# vu_esquema.net
KiCad netlist of a schematic drawn in EAGLE
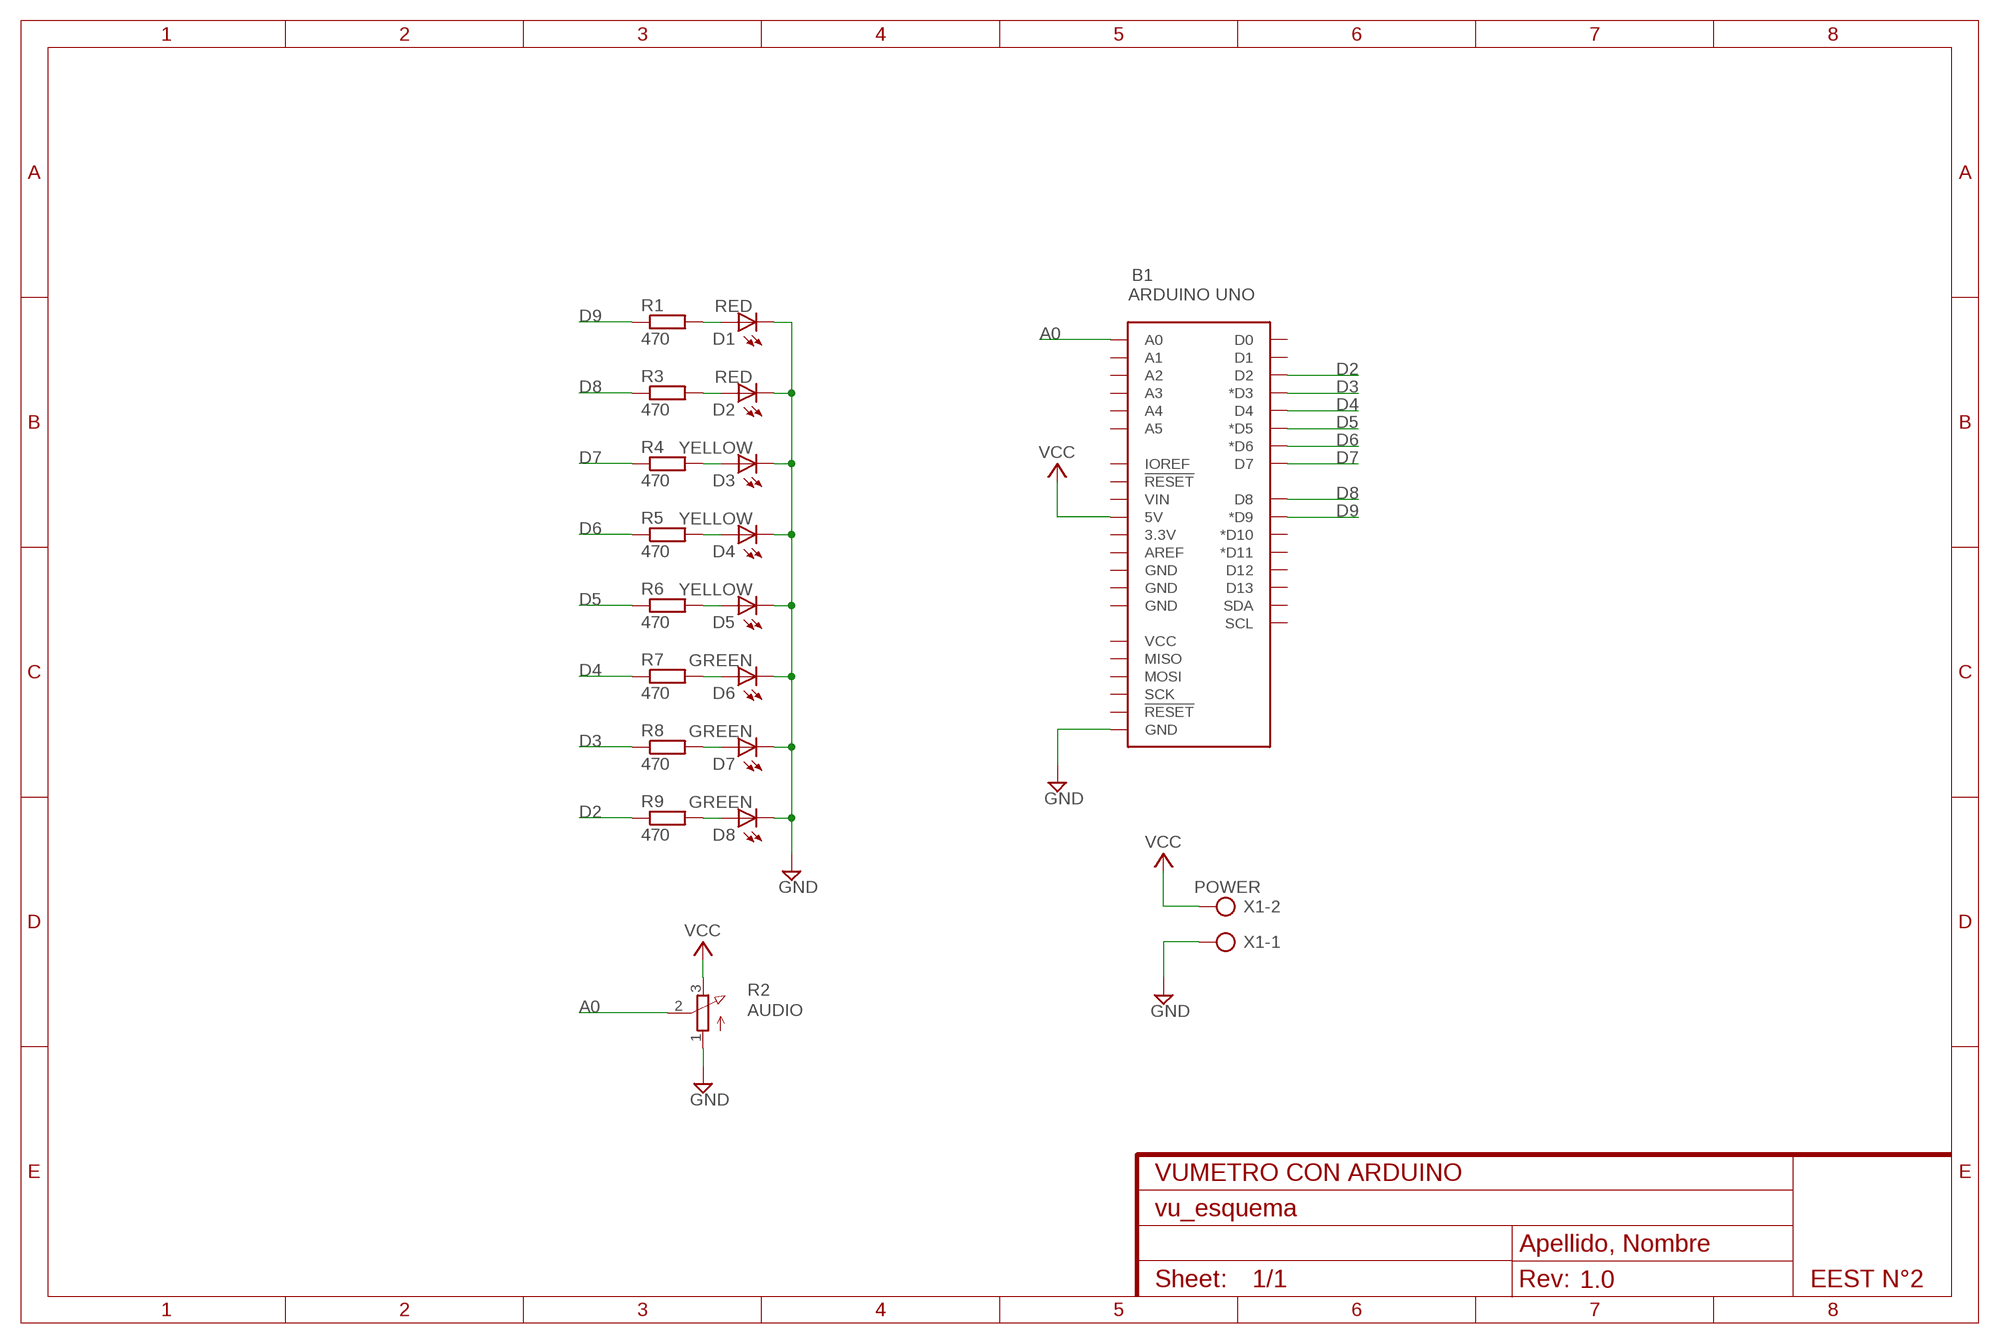
[diagram p0: schematic, sheet 1]

(export (version "E")
  (design (tool "Eeschema 10.0.6"))
  (components
    (comp (ref "B1")
      (value "ARDUINO UNO")
      (footprint "eagle-import:ARDUINO_R3")
      (libsource (lib "eagle-import") (part "ARDUINO_UNO_R3"))
    )
    (comp (ref "D1")
      (value "RED")
      (footprint "eagle-import:LED_5MM")
      (libsource (lib "eagle-import") (part "LED5MM"))
    )
    (comp (ref "D2")
      (value "RED")
      (footprint "eagle-import:LED_5MM")
      (libsource (lib "eagle-import") (part "LED5MM"))
    )
    (comp (ref "D3")
      (value "YELLOW")
      (footprint "eagle-import:LED_5MM")
      (libsource (lib "eagle-import") (part "LED5MM"))
    )
    (comp (ref "D4")
      (value "YELLOW")
      (footprint "eagle-import:LED_5MM")
      (libsource (lib "eagle-import") (part "LED5MM"))
    )
    (comp (ref "D5")
      (value "YELLOW")
      (footprint "eagle-import:LED_5MM")
      (libsource (lib "eagle-import") (part "LED5MM"))
    )
    (comp (ref "D6")
      (value "GREEN")
      (footprint "eagle-import:LED_5MM")
      (libsource (lib "eagle-import") (part "LED5MM"))
    )
    (comp (ref "D7")
      (value "GREEN")
      (footprint "eagle-import:LED_5MM")
      (libsource (lib "eagle-import") (part "LED5MM"))
    )
    (comp (ref "D8")
      (value "GREEN")
      (footprint "eagle-import:LED_5MM")
      (libsource (lib "eagle-import") (part "LED5MM"))
    )
    (comp (ref "R1")
      (value "470")
      (footprint "eagle-import:0204_7")
      (libsource (lib "eagle-import") (part "RESISTOR-EU0204/7"))
    )
    (comp (ref "R2")
      (value "AUDIO")
      (footprint "eagle-import:3RP_1610N")
      (libsource (lib "eagle-import") (part "3RP/1610N"))
    )
    (comp (ref "R3")
      (value "470")
      (footprint "eagle-import:0204_7")
      (libsource (lib "eagle-import") (part "RESISTOR-EU0204/7"))
    )
    (comp (ref "R4")
      (value "470")
      (footprint "eagle-import:0204_7")
      (libsource (lib "eagle-import") (part "RESISTOR-EU0204/7"))
    )
    (comp (ref "R5")
      (value "470")
      (footprint "eagle-import:0204_7")
      (libsource (lib "eagle-import") (part "RESISTOR-EU0204/7"))
    )
    (comp (ref "R6")
      (value "470")
      (footprint "eagle-import:0204_7")
      (libsource (lib "eagle-import") (part "RESISTOR-EU0204/7"))
    )
    (comp (ref "R7")
      (value "470")
      (footprint "eagle-import:0204_7")
      (libsource (lib "eagle-import") (part "RESISTOR-EU0204/7"))
    )
    (comp (ref "R8")
      (value "470")
      (footprint "eagle-import:0204_7")
      (libsource (lib "eagle-import") (part "RESISTOR-EU0204/7"))
    )
    (comp (ref "R9")
      (value "470")
      (footprint "eagle-import:0204_7")
      (libsource (lib "eagle-import") (part "RESISTOR-EU0204/7"))
    )
    (comp (ref "X1")
      (value "POWER")
      (footprint "eagle-import:AK500_2")
      (libsource (lib "eagle-import") (part "BORNERA_AK500/2"))
    )
  )
  (nets
    (net (code "1") (name "/A0") (class "Default")
      (node (ref "B1") (pin "A0") (pinfunction "A0_A0") (pintype "bidirectional"))
      (node (ref "R2") (pin "2") (pinfunction "S_2") (pintype "passive"))
    )
    (net (code "2") (name "/D2") (class "Default")
      (node (ref "B1") (pin "D2") (pinfunction "D2_D2") (pintype "bidirectional"))
      (node (ref "R9") (pin "1") (pinfunction "1_1") (pintype "passive"))
    )
    (net (code "3") (name "/D3") (class "Default")
      (node (ref "B1") (pin "D3") (pinfunction "*D3_D3") (pintype "bidirectional"))
      (node (ref "R8") (pin "1") (pinfunction "1_1") (pintype "passive"))
    )
    (net (code "4") (name "/D4") (class "Default")
      (node (ref "B1") (pin "D4") (pinfunction "D4_D4") (pintype "bidirectional"))
      (node (ref "R7") (pin "1") (pinfunction "1_1") (pintype "passive"))
    )
    (net (code "5") (name "/D5") (class "Default")
      (node (ref "B1") (pin "D5") (pinfunction "*D5_D5") (pintype "bidirectional"))
      (node (ref "R6") (pin "1") (pinfunction "1_1") (pintype "passive"))
    )
    (net (code "6") (name "/D6") (class "Default")
      (node (ref "B1") (pin "D6") (pinfunction "*D6_D6") (pintype "bidirectional"))
      (node (ref "R5") (pin "1") (pinfunction "1_1") (pintype "passive"))
    )
    (net (code "7") (name "/D7") (class "Default")
      (node (ref "B1") (pin "D7") (pinfunction "D7_D7") (pintype "bidirectional"))
      (node (ref "R4") (pin "1") (pinfunction "1_1") (pintype "passive"))
    )
    (net (code "8") (name "/D8") (class "Default")
      (node (ref "B1") (pin "D8") (pinfunction "D8_D8") (pintype "bidirectional"))
      (node (ref "R3") (pin "1") (pinfunction "1_1") (pintype "passive"))
    )
    (net (code "9") (name "/D9") (class "Default")
      (node (ref "B1") (pin "D9") (pinfunction "*D9_D9") (pintype "bidirectional"))
      (node (ref "R1") (pin "1") (pinfunction "1_1") (pintype "passive"))
    )
    (net (code "10") (name "GND") (class "Default")
      (node (ref "B1") (pin "GND@1") (pinfunction "GND_GND@1") (pintype "bidirectional"))
      (node (ref "D1") (pin "K") (pinfunction "C_K") (pintype "passive"))
      (node (ref "D2") (pin "K") (pinfunction "C_K") (pintype "passive"))
      (node (ref "D3") (pin "K") (pinfunction "C_K") (pintype "passive"))
      (node (ref "D4") (pin "K") (pinfunction "C_K") (pintype "passive"))
      (node (ref "D5") (pin "K") (pinfunction "C_K") (pintype "passive"))
      (node (ref "D6") (pin "K") (pinfunction "C_K") (pintype "passive"))
      (node (ref "D7") (pin "K") (pinfunction "C_K") (pintype "passive"))
      (node (ref "D8") (pin "K") (pinfunction "C_K") (pintype "passive"))
      (node (ref "R2") (pin "1") (pinfunction "A_1") (pintype "passive"))
      (node (ref "X1") (pin "1") (pinfunction "KL_1") (pintype "passive"))
    )
    (net (code "11") (name "Net-(D1-PadA)") (class "Default")
      (node (ref "D1") (pin "A") (pinfunction "A_A") (pintype "passive"))
      (node (ref "R1") (pin "2") (pinfunction "2_2") (pintype "passive"))
    )
    (net (code "12") (name "Net-(D2-PadA)") (class "Default")
      (node (ref "D2") (pin "A") (pinfunction "A_A") (pintype "passive"))
      (node (ref "R3") (pin "2") (pinfunction "2_2") (pintype "passive"))
    )
    (net (code "13") (name "Net-(D3-PadA)") (class "Default")
      (node (ref "D3") (pin "A") (pinfunction "A_A") (pintype "passive"))
      (node (ref "R4") (pin "2") (pinfunction "2_2") (pintype "passive"))
    )
    (net (code "14") (name "Net-(D4-PadA)") (class "Default")
      (node (ref "D4") (pin "A") (pinfunction "A_A") (pintype "passive"))
      (node (ref "R5") (pin "2") (pinfunction "2_2") (pintype "passive"))
    )
    (net (code "15") (name "Net-(D5-PadA)") (class "Default")
      (node (ref "D5") (pin "A") (pinfunction "A_A") (pintype "passive"))
      (node (ref "R6") (pin "2") (pinfunction "2_2") (pintype "passive"))
    )
    (net (code "16") (name "Net-(D6-PadA)") (class "Default")
      (node (ref "D6") (pin "A") (pinfunction "A_A") (pintype "passive"))
      (node (ref "R7") (pin "2") (pinfunction "2_2") (pintype "passive"))
    )
    (net (code "17") (name "Net-(D7-PadA)") (class "Default")
      (node (ref "D7") (pin "A") (pinfunction "A_A") (pintype "passive"))
      (node (ref "R8") (pin "2") (pinfunction "2_2") (pintype "passive"))
    )
    (net (code "18") (name "Net-(D8-PadA)") (class "Default")
      (node (ref "D8") (pin "A") (pinfunction "A_A") (pintype "passive"))
      (node (ref "R9") (pin "2") (pinfunction "2_2") (pintype "passive"))
    )
    (net (code "19") (name "VCC") (class "Default")
      (node (ref "B1") (pin "5V") (pinfunction "5V_5V") (pintype "bidirectional"))
      (node (ref "R2") (pin "3") (pinfunction "E_3") (pintype "passive"))
      (node (ref "X1") (pin "2") (pinfunction "KL_2") (pintype "passive"))
    )
    (net (code "20") (name "unconnected-(B1-*D10-PadD10)") (class "Default")
      (node (ref "B1") (pin "D10") (pinfunction "*D10_D10") (pintype "bidirectional"))
    )
    (net (code "21") (name "unconnected-(B1-*D11-PadD11)") (class "Default")
      (node (ref "B1") (pin "D11") (pinfunction "*D11_D11") (pintype "bidirectional"))
    )
    (net (code "22") (name "unconnected-(B1-GND-PadGND@2)") (class "Default")
      (node (ref "B1") (pin "GND@2") (pinfunction "GND_GND@2") (pintype "bidirectional"))
    )
    (net (code "23") (name "unconnected-(B1-GND-PadGND@3)") (class "Default")
      (node (ref "B1") (pin "GND@3") (pinfunction "GND_GND@3") (pintype "bidirectional"))
    )
    (net (code "24") (name "unconnected-(B1-GND-PadGND@4)") (class "Default")
      (node (ref "B1") (pin "GND@4") (pinfunction "GND_GND@4") (pintype "bidirectional"))
    )
    (net (code "25") (name "unconnected-(B1-Pad3.3V)") (class "Default")
      (node (ref "B1") (pin "3.3V") (pinfunction "3.3V_3.3V") (pintype "bidirectional"))
    )
    (net (code "26") (name "unconnected-(B1-PadA1)") (class "Default")
      (node (ref "B1") (pin "A1") (pinfunction "A1_A1") (pintype "bidirectional"))
    )
    (net (code "27") (name "unconnected-(B1-PadA2)") (class "Default")
      (node (ref "B1") (pin "A2") (pinfunction "A2_A2") (pintype "bidirectional"))
    )
    (net (code "28") (name "unconnected-(B1-PadA3)") (class "Default")
      (node (ref "B1") (pin "A3") (pinfunction "A3_A3") (pintype "bidirectional"))
    )
    (net (code "29") (name "unconnected-(B1-PadA4)") (class "Default")
      (node (ref "B1") (pin "A4") (pinfunction "A4_A4") (pintype "bidirectional"))
    )
    (net (code "30") (name "unconnected-(B1-PadA5)") (class "Default")
      (node (ref "B1") (pin "A5") (pinfunction "A5_A5") (pintype "bidirectional"))
    )
    (net (code "31") (name "unconnected-(B1-PadAREF)") (class "Default")
      (node (ref "B1") (pin "AREF") (pinfunction "AREF_AREF") (pintype "bidirectional"))
    )
    (net (code "32") (name "unconnected-(B1-PadD0)") (class "Default")
      (node (ref "B1") (pin "D0") (pinfunction "D0_D0") (pintype "bidirectional"))
    )
    (net (code "33") (name "unconnected-(B1-PadD1)") (class "Default")
      (node (ref "B1") (pin "D1") (pinfunction "D1_D1") (pintype "bidirectional"))
    )
    (net (code "34") (name "unconnected-(B1-PadD12)") (class "Default")
      (node (ref "B1") (pin "D12") (pinfunction "D12_D12") (pintype "bidirectional"))
    )
    (net (code "35") (name "unconnected-(B1-PadD13)") (class "Default")
      (node (ref "B1") (pin "D13") (pinfunction "D13_D13") (pintype "bidirectional"))
    )
    (net (code "36") (name "unconnected-(B1-PadIOREF)") (class "Default")
      (node (ref "B1") (pin "IOREF") (pinfunction "IOREF_IOREF") (pintype "bidirectional"))
    )
    (net (code "37") (name "unconnected-(B1-PadMISO)") (class "Default")
      (node (ref "B1") (pin "MISO") (pinfunction "MISO_MISO") (pintype "bidirectional"))
    )
    (net (code "38") (name "unconnected-(B1-PadMOSI)") (class "Default")
      (node (ref "B1") (pin "MOSI") (pinfunction "MOSI_MOSI") (pintype "bidirectional"))
    )
    (net (code "39") (name "unconnected-(B1-PadSCK)") (class "Default")
      (node (ref "B1") (pin "SCK") (pinfunction "SCK_SCK") (pintype "bidirectional"))
    )
    (net (code "40") (name "unconnected-(B1-PadSCL)") (class "Default")
      (node (ref "B1") (pin "SCL") (pinfunction "SCL_SCL") (pintype "bidirectional"))
    )
    (net (code "41") (name "unconnected-(B1-PadSDA)") (class "Default")
      (node (ref "B1") (pin "SDA") (pinfunction "SDA_SDA") (pintype "bidirectional"))
    )
    (net (code "42") (name "unconnected-(B1-PadVCC)") (class "Default")
      (node (ref "B1") (pin "VCC") (pinfunction "VCC_VCC") (pintype "bidirectional"))
    )
    (net (code "43") (name "unconnected-(B1-PadVIN)") (class "Default")
      (node (ref "B1") (pin "VIN") (pinfunction "VIN_VIN") (pintype "bidirectional"))
    )
    (net (code "44") (name "unconnected-(B1-~{RESET}-PadRESET@1)") (class "Default")
      (node (ref "B1") (pin "RESET@1") (pinfunction "~{RESET}_RESET@1") (pintype "bidirectional"))
    )
    (net (code "45") (name "unconnected-(B1-~{RESET}-PadRESET@2)") (class "Default")
      (node (ref "B1") (pin "RESET@2") (pinfunction "~{RESET}_RESET@2") (pintype "bidirectional"))
    )
  )
)
